# POWER.net
KiCad netlist of a schematic drawn in Altium Designer
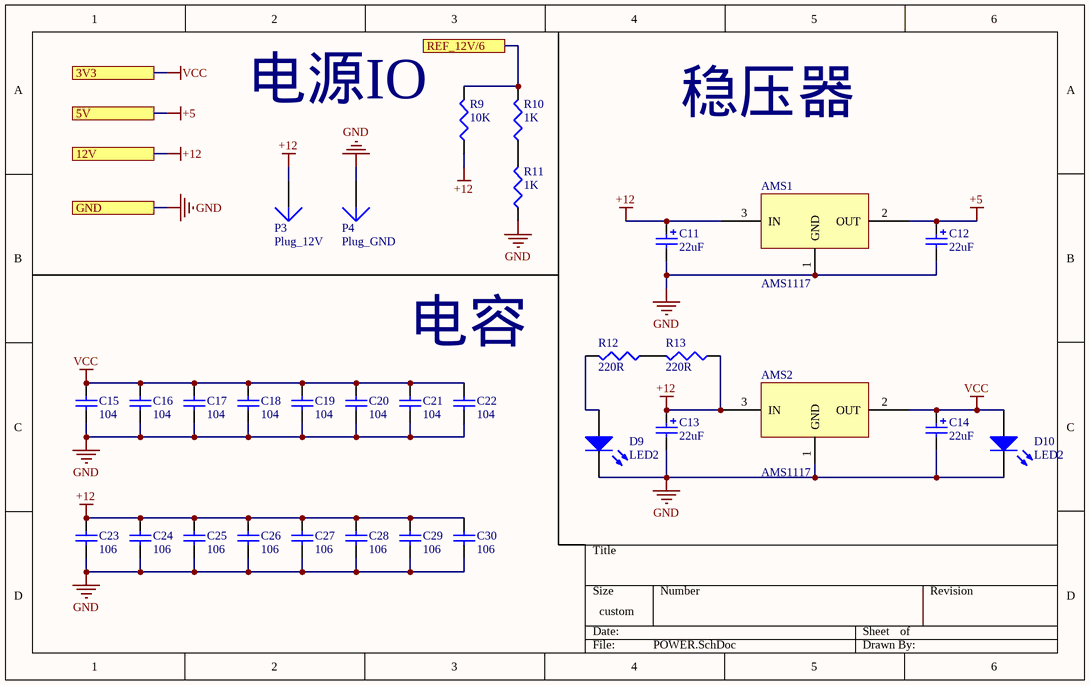
[diagram p0: POWER.SchDoc]

(export (version "E")
  (design (tool "Eeschema 10.0.6"))
  (components
    (comp (ref "AMS1") (value "AMS1117") (footprint "AMS1117") (libsource (lib "Schlib1") (part "AMS1117")))
    (comp (ref "AMS2") (value "AMS1117") (footprint "AMS1117") (libsource (lib "Schlib1") (part "AMS1117")))
    (comp (ref "C11")
      (value "22uF")
      (footprint "MY0805")
      (description "Polarized Capacitor (Axial)")
      (fields (field (name "PUBLISHER") "Altium Limited"))
      (libsource (lib "Miscellaneous Devices") (part "Cap Pol2"))
    )
    (comp (ref "C12")
      (value "22uF")
      (footprint "MY0805")
      (description "Polarized Capacitor (Axial)")
      (fields (field (name "PUBLISHER") "Altium Limited"))
      (libsource (lib "Miscellaneous Devices") (part "Cap Pol2"))
    )
    (comp (ref "C13")
      (value "22uF")
      (footprint "MY0805")
      (description "Polarized Capacitor (Axial)")
      (fields (field (name "PUBLISHER") "Altium Limited"))
      (libsource (lib "Miscellaneous Devices") (part "Cap Pol2"))
    )
    (comp (ref "C14")
      (value "22uF")
      (footprint "MY0805")
      (description "Polarized Capacitor (Axial)")
      (fields (field (name "PUBLISHER") "Altium Limited"))
      (libsource (lib "Miscellaneous Devices") (part "Cap Pol2"))
    )
    (comp (ref "C15")
      (value "104")
      (footprint "MY0805")
      (description "Capacitor")
      (fields (field (name "PUBLISHER") "Altium Limited"))
      (libsource (lib "Miscellaneous Devices") (part "Cap"))
    )
    (comp (ref "C16")
      (value "104")
      (footprint "MY0805")
      (description "Capacitor")
      (fields (field (name "PUBLISHER") "Altium Limited"))
      (libsource (lib "Miscellaneous Devices") (part "Cap"))
    )
    (comp (ref "C17")
      (value "104")
      (footprint "MY0805")
      (description "Capacitor")
      (fields (field (name "PUBLISHER") "Altium Limited"))
      (libsource (lib "Miscellaneous Devices") (part "Cap"))
    )
    (comp (ref "C18")
      (value "104")
      (footprint "MY0805")
      (description "Capacitor")
      (fields (field (name "PUBLISHER") "Altium Limited"))
      (libsource (lib "Miscellaneous Devices") (part "Cap"))
    )
    (comp (ref "C19")
      (value "104")
      (footprint "MY0805")
      (description "Capacitor")
      (fields (field (name "PUBLISHER") "Altium Limited"))
      (libsource (lib "Miscellaneous Devices") (part "Cap"))
    )
    (comp (ref "C20")
      (value "104")
      (footprint "MY0805")
      (description "Capacitor")
      (fields (field (name "PUBLISHER") "Altium Limited"))
      (libsource (lib "Miscellaneous Devices") (part "Cap"))
    )
    (comp (ref "C21")
      (value "104")
      (footprint "MY0805")
      (description "Capacitor")
      (fields (field (name "PUBLISHER") "Altium Limited"))
      (libsource (lib "Miscellaneous Devices") (part "Cap"))
    )
    (comp (ref "C22")
      (value "104")
      (footprint "MY0805")
      (description "Capacitor")
      (fields (field (name "PUBLISHER") "Altium Limited"))
      (libsource (lib "Miscellaneous Devices") (part "Cap"))
    )
    (comp (ref "C23")
      (value "106")
      (footprint "MY0805")
      (description "Capacitor")
      (fields (field (name "PUBLISHER") "Altium Limited"))
      (libsource (lib "Miscellaneous Devices") (part "Cap"))
    )
    (comp (ref "C24")
      (value "106")
      (footprint "MY0805")
      (description "Capacitor")
      (fields (field (name "PUBLISHER") "Altium Limited"))
      (libsource (lib "Miscellaneous Devices") (part "Cap"))
    )
    (comp (ref "C25")
      (value "106")
      (footprint "MY0805")
      (description "Capacitor")
      (fields (field (name "PUBLISHER") "Altium Limited"))
      (libsource (lib "Miscellaneous Devices") (part "Cap"))
    )
    (comp (ref "C26")
      (value "106")
      (footprint "MY0805")
      (description "Capacitor")
      (fields (field (name "PUBLISHER") "Altium Limited"))
      (libsource (lib "Miscellaneous Devices") (part "Cap"))
    )
    (comp (ref "C27")
      (value "106")
      (footprint "MY0805")
      (description "Capacitor")
      (fields (field (name "PUBLISHER") "Altium Limited"))
      (libsource (lib "Miscellaneous Devices") (part "Cap"))
    )
    (comp (ref "C28")
      (value "106")
      (footprint "MY0805")
      (description "Capacitor")
      (fields (field (name "PUBLISHER") "Altium Limited"))
      (libsource (lib "Miscellaneous Devices") (part "Cap"))
    )
    (comp (ref "C29")
      (value "106")
      (footprint "MY0805")
      (description "Capacitor")
      (fields (field (name "PUBLISHER") "Altium Limited"))
      (libsource (lib "Miscellaneous Devices") (part "Cap"))
    )
    (comp (ref "C30")
      (value "106")
      (footprint "MY0805")
      (description "Capacitor")
      (fields (field (name "PUBLISHER") "Altium Limited"))
      (libsource (lib "Miscellaneous Devices") (part "Cap"))
    )
    (comp (ref "D9")
      (value "LED2")
      (footprint "MY0805")
      (description "Typical RED, GREEN, YELLOW, AMBER GaAs LED")
      (fields (field (name "PUBLISHER") "Altium Limited"))
      (libsource (lib "Miscellaneous Devices") (part "LED2"))
    )
    (comp (ref "D10")
      (value "LED2")
      (footprint "MY0805")
      (description "Typical RED, GREEN, YELLOW, AMBER GaAs LED")
      (fields (field (name "PUBLISHER") "Altium Limited"))
      (libsource (lib "Miscellaneous Devices") (part "LED2"))
    )
    (comp (ref "P3")
      (value "Plug_12V")
      (footprint "Hole_3MM")
      (fields (field (name "PUBLISHER") "Altium Limited"))
      (libsource (lib "Miscellaneous Connectors") (part "Plug"))
    )
    (comp (ref "P4")
      (value "Plug_GND")
      (footprint "Hole_3MM")
      (description "Plug")
      (fields (field (name "PUBLISHER") "Altium Limited"))
      (libsource (lib "Miscellaneous Connectors") (part "Plug"))
    )
    (comp (ref "R9")
      (value "10K")
      (footprint "MY0805")
      (description "Resistor")
      (fields (field (name "PUBLISHER") "Altium Limited"))
      (libsource (lib "Miscellaneous Devices") (part "Res3"))
    )
    (comp (ref "R10")
      (value "1K")
      (footprint "MY0805")
      (description "Resistor")
      (fields (field (name "PUBLISHER") "Altium Limited"))
      (libsource (lib "Miscellaneous Devices") (part "Res3"))
    )
    (comp (ref "R11")
      (value "1K")
      (footprint "MY0805")
      (description "Resistor")
      (fields (field (name "PUBLISHER") "Altium Limited"))
      (libsource (lib "Miscellaneous Devices") (part "Res3"))
    )
    (comp (ref "R12")
      (value "220R")
      (footprint "MY0805")
      (description "Resistor")
      (fields (field (name "PUBLISHER") "Altium Limited"))
      (libsource (lib "Miscellaneous Devices") (part "Res3"))
    )
    (comp (ref "R13")
      (value "220R")
      (footprint "MY0805")
      (description "Resistor")
      (fields (field (name "PUBLISHER") "Altium Limited"))
      (libsource (lib "Miscellaneous Devices") (part "Res3"))
    )
  )
  (nets
    (net (code "1") (name "+5") (class "Default")
      (node (ref "AMS1") (pin "2") (pinfunction "OUT_2") (pintype "passive"))
      (node (ref "C12") (pin "1") (pinfunction "1_1") (pintype "passive"))
    )
    (net (code "2") (name "+12") (class "Default")
      (node (ref "AMS1") (pin "3") (pinfunction "IN_3") (pintype "passive"))
      (node (ref "AMS2") (pin "3") (pinfunction "IN_3") (pintype "passive"))
      (node (ref "C11") (pin "1") (pinfunction "1_1") (pintype "passive"))
      (node (ref "C13") (pin "1") (pinfunction "1_1") (pintype "passive"))
      (node (ref "C23") (pin "2") (pinfunction "2_2") (pintype "passive"))
      (node (ref "C24") (pin "2") (pinfunction "2_2") (pintype "passive"))
      (node (ref "C25") (pin "2") (pinfunction "2_2") (pintype "passive"))
      (node (ref "C26") (pin "2") (pinfunction "2_2") (pintype "passive"))
      (node (ref "C27") (pin "2") (pinfunction "2_2") (pintype "passive"))
      (node (ref "C28") (pin "2") (pinfunction "2_2") (pintype "passive"))
      (node (ref "C29") (pin "2") (pinfunction "2_2") (pintype "passive"))
      (node (ref "C30") (pin "2") (pinfunction "2_2") (pintype "passive"))
      (node (ref "P3") (pin "1") (pinfunction "1_1") (pintype "passive"))
      (node (ref "R13") (pin "1") (pinfunction "1_1") (pintype "passive"))
      (node (ref "R9") (pin "1") (pinfunction "1_1") (pintype "passive"))
    )
    (net (code "3") (name "/REF_12V{slash}6") (class "Default")
      (node (ref "R10") (pin "2") (pinfunction "2_2") (pintype "passive"))
      (node (ref "R9") (pin "2") (pinfunction "2_2") (pintype "passive"))
    )
    (net (code "4") (name "GND") (class "Default")
      (node (ref "AMS1") (pin "1") (pinfunction "GND_1") (pintype "passive"))
      (node (ref "AMS2") (pin "1") (pinfunction "GND_1") (pintype "passive"))
      (node (ref "C11") (pin "2") (pinfunction "2_2") (pintype "passive"))
      (node (ref "C12") (pin "2") (pinfunction "2_2") (pintype "passive"))
      (node (ref "C13") (pin "2") (pinfunction "2_2") (pintype "passive"))
      (node (ref "C14") (pin "2") (pinfunction "2_2") (pintype "passive"))
      (node (ref "C15") (pin "1") (pinfunction "1_1") (pintype "passive"))
      (node (ref "C16") (pin "1") (pinfunction "1_1") (pintype "passive"))
      (node (ref "C17") (pin "1") (pinfunction "1_1") (pintype "passive"))
      (node (ref "C18") (pin "1") (pinfunction "1_1") (pintype "passive"))
      (node (ref "C19") (pin "1") (pinfunction "1_1") (pintype "passive"))
      (node (ref "C20") (pin "1") (pinfunction "1_1") (pintype "passive"))
      (node (ref "C21") (pin "1") (pinfunction "1_1") (pintype "passive"))
      (node (ref "C22") (pin "1") (pinfunction "1_1") (pintype "passive"))
      (node (ref "C23") (pin "1") (pinfunction "1_1") (pintype "passive"))
      (node (ref "C24") (pin "1") (pinfunction "1_1") (pintype "passive"))
      (node (ref "C25") (pin "1") (pinfunction "1_1") (pintype "passive"))
      (node (ref "C26") (pin "1") (pinfunction "1_1") (pintype "passive"))
      (node (ref "C27") (pin "1") (pinfunction "1_1") (pintype "passive"))
      (node (ref "C28") (pin "1") (pinfunction "1_1") (pintype "passive"))
      (node (ref "C29") (pin "1") (pinfunction "1_1") (pintype "passive"))
      (node (ref "C30") (pin "1") (pinfunction "1_1") (pintype "passive"))
      (node (ref "D10") (pin "2") (pinfunction "K_2") (pintype "passive"))
      (node (ref "D9") (pin "2") (pinfunction "K_2") (pintype "passive"))
      (node (ref "P4") (pin "1") (pinfunction "1_1") (pintype "passive"))
      (node (ref "R11") (pin "1") (pinfunction "1_1") (pintype "passive"))
    )
    (net (code "5") (name "Net-(D9-A)") (class "Default")
      (node (ref "D9") (pin "1") (pinfunction "A_1") (pintype "passive"))
      (node (ref "R12") (pin "2") (pinfunction "2_2") (pintype "passive"))
    )
    (net (code "6") (name "Net-(R10-Pad1)") (class "Default")
      (node (ref "R10") (pin "1") (pinfunction "1_1") (pintype "passive"))
      (node (ref "R11") (pin "2") (pinfunction "2_2") (pintype "passive"))
    )
    (net (code "7") (name "Net-(R12-Pad1)") (class "Default")
      (node (ref "R12") (pin "1") (pinfunction "1_1") (pintype "passive"))
      (node (ref "R13") (pin "2") (pinfunction "2_2") (pintype "passive"))
    )
    (net (code "8") (name "VCC") (class "Default")
      (node (ref "AMS2") (pin "2") (pinfunction "OUT_2") (pintype "passive"))
      (node (ref "C14") (pin "1") (pinfunction "1_1") (pintype "passive"))
      (node (ref "C15") (pin "2") (pinfunction "2_2") (pintype "passive"))
      (node (ref "C16") (pin "2") (pinfunction "2_2") (pintype "passive"))
      (node (ref "C17") (pin "2") (pinfunction "2_2") (pintype "passive"))
      (node (ref "C18") (pin "2") (pinfunction "2_2") (pintype "passive"))
      (node (ref "C19") (pin "2") (pinfunction "2_2") (pintype "passive"))
      (node (ref "C20") (pin "2") (pinfunction "2_2") (pintype "passive"))
      (node (ref "C21") (pin "2") (pinfunction "2_2") (pintype "passive"))
      (node (ref "C22") (pin "2") (pinfunction "2_2") (pintype "passive"))
      (node (ref "D10") (pin "1") (pinfunction "A_1") (pintype "passive"))
    )
  )
)
